# MAD.net
KiCad netlist of a schematic drawn in EAGLE
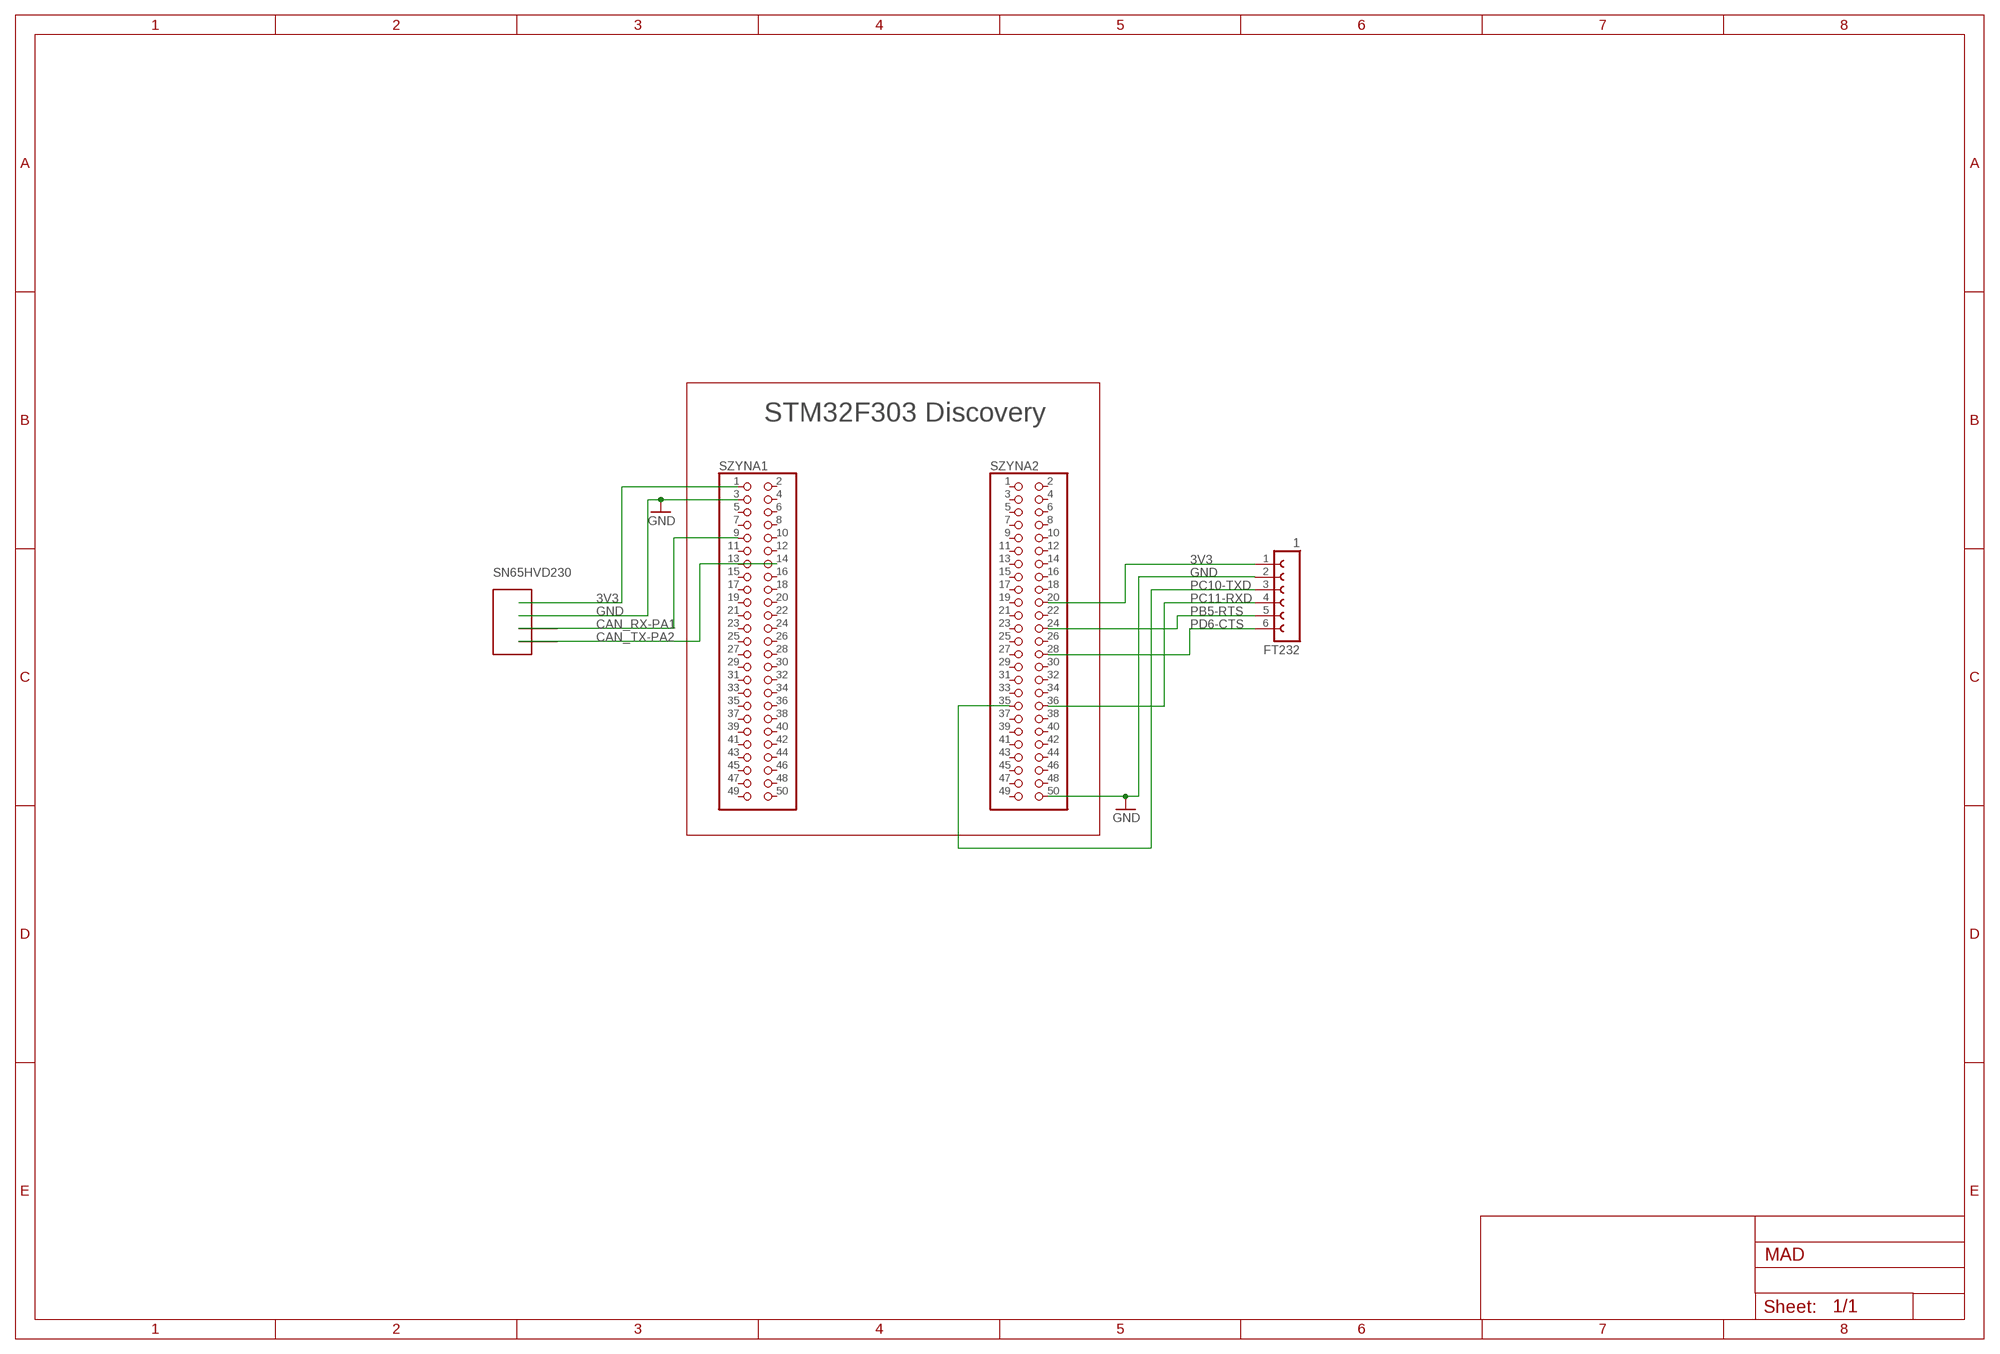
[diagram p0: schematic, sheet 1]

(export (version "E")
  (design (tool "Eeschema 10.0.6"))
  (components
    (comp (ref "FT232")
      (value "1")
      (footprint "eagle-import:FE06W")
      (libsource (lib "eagle-import") (part "FE06W"))
    )
    (comp (ref "SN65HVD230")
      (value "FE04W")
      (footprint "eagle-import:FE04")
      (libsource (lib "eagle-import") (part "FE04W"))
    )
    (comp (ref "SZYNA1")
      (value "PINHD-2X25")
      (footprint "eagle-import:2X25")
      (libsource (lib "eagle-import") (part "PINHD-2X25"))
    )
    (comp (ref "SZYNA2")
      (value "PINHD-2X25")
      (footprint "eagle-import:2X25")
      (libsource (lib "eagle-import") (part "PINHD-2X25"))
    )
  )
  (nets
    (net (code "1") (name "GND") (class "Default")
      (node (ref "FT232") (pin "2") (pinfunction "2_2") (pintype "passive"))
      (node (ref "SN65HVD230") (pin "P$2") (pinfunction "P$2_P$2") (pintype "bidirectional"))
      (node (ref "SZYNA1") (pin "3") (pinfunction "3_3") (pintype "passive"))
      (node (ref "SZYNA2") (pin "50") (pinfunction "50_50") (pintype "passive"))
    )
    (net (code "2") (name "Net-(FT232-Pad1)") (class "Default")
      (node (ref "FT232") (pin "1") (pinfunction "1_1") (pintype "passive"))
      (node (ref "SZYNA2") (pin "20") (pinfunction "20_20") (pintype "passive"))
    )
    (net (code "3") (name "Net-(FT232-Pad3)") (class "Default")
      (node (ref "FT232") (pin "3") (pinfunction "3_3") (pintype "passive"))
      (node (ref "SZYNA2") (pin "35") (pinfunction "35_35") (pintype "passive"))
    )
    (net (code "4") (name "Net-(FT232-Pad4)") (class "Default")
      (node (ref "FT232") (pin "4") (pinfunction "4_4") (pintype "passive"))
      (node (ref "SZYNA2") (pin "36") (pinfunction "36_36") (pintype "passive"))
    )
    (net (code "5") (name "Net-(FT232-Pad5)") (class "Default")
      (node (ref "FT232") (pin "5") (pinfunction "5_5") (pintype "passive"))
      (node (ref "SZYNA2") (pin "24") (pinfunction "24_24") (pintype "passive"))
    )
    (net (code "6") (name "Net-(FT232-Pad6)") (class "Default")
      (node (ref "FT232") (pin "6") (pinfunction "6_6") (pintype "passive"))
      (node (ref "SZYNA2") (pin "28") (pinfunction "28_28") (pintype "passive"))
    )
    (net (code "7") (name "Net-(SN65HVD230-PadP$1)") (class "Default")
      (node (ref "SN65HVD230") (pin "P$1") (pinfunction "P$1_P$1") (pintype "bidirectional"))
      (node (ref "SZYNA1") (pin "1") (pinfunction "1_1") (pintype "passive"))
    )
    (net (code "8") (name "Net-(SN65HVD230-PadP$3)") (class "Default")
      (node (ref "SN65HVD230") (pin "P$3") (pinfunction "P$3_P$3") (pintype "bidirectional"))
      (node (ref "SZYNA1") (pin "9") (pinfunction "9_9") (pintype "passive"))
    )
    (net (code "9") (name "Net-(SN65HVD230-PadP$4)") (class "Default")
      (node (ref "SN65HVD230") (pin "P$4") (pinfunction "P$4_P$4") (pintype "bidirectional"))
      (node (ref "SZYNA1") (pin "14") (pinfunction "14_14") (pintype "passive"))
    )
    (net (code "10") (name "unconnected-(SZYNA1-Pad2)") (class "Default")
      (node (ref "SZYNA1") (pin "2") (pinfunction "2_2") (pintype "passive"))
    )
    (net (code "11") (name "unconnected-(SZYNA1-Pad4)") (class "Default")
      (node (ref "SZYNA1") (pin "4") (pinfunction "4_4") (pintype "passive"))
    )
    (net (code "12") (name "unconnected-(SZYNA1-Pad5)") (class "Default")
      (node (ref "SZYNA1") (pin "5") (pinfunction "5_5") (pintype "passive"))
    )
    (net (code "13") (name "unconnected-(SZYNA1-Pad6)") (class "Default")
      (node (ref "SZYNA1") (pin "6") (pinfunction "6_6") (pintype "passive"))
    )
    (net (code "14") (name "unconnected-(SZYNA1-Pad7)") (class "Default")
      (node (ref "SZYNA1") (pin "7") (pinfunction "7_7") (pintype "passive"))
    )
    (net (code "15") (name "unconnected-(SZYNA1-Pad8)") (class "Default")
      (node (ref "SZYNA1") (pin "8") (pinfunction "8_8") (pintype "passive"))
    )
    (net (code "16") (name "unconnected-(SZYNA1-Pad10)") (class "Default")
      (node (ref "SZYNA1") (pin "10") (pinfunction "10_10") (pintype "passive"))
    )
    (net (code "17") (name "unconnected-(SZYNA1-Pad11)") (class "Default")
      (node (ref "SZYNA1") (pin "11") (pinfunction "11_11") (pintype "passive"))
    )
    (net (code "18") (name "unconnected-(SZYNA1-Pad12)") (class "Default")
      (node (ref "SZYNA1") (pin "12") (pinfunction "12_12") (pintype "passive"))
    )
    (net (code "19") (name "unconnected-(SZYNA1-Pad13)") (class "Default")
      (node (ref "SZYNA1") (pin "13") (pinfunction "13_13") (pintype "passive"))
    )
    (net (code "20") (name "unconnected-(SZYNA1-Pad15)") (class "Default")
      (node (ref "SZYNA1") (pin "15") (pinfunction "15_15") (pintype "passive"))
    )
    (net (code "21") (name "unconnected-(SZYNA1-Pad16)") (class "Default")
      (node (ref "SZYNA1") (pin "16") (pinfunction "16_16") (pintype "passive"))
    )
    (net (code "22") (name "unconnected-(SZYNA1-Pad17)") (class "Default")
      (node (ref "SZYNA1") (pin "17") (pinfunction "17_17") (pintype "passive"))
    )
    (net (code "23") (name "unconnected-(SZYNA1-Pad18)") (class "Default")
      (node (ref "SZYNA1") (pin "18") (pinfunction "18_18") (pintype "passive"))
    )
    (net (code "24") (name "unconnected-(SZYNA1-Pad19)") (class "Default")
      (node (ref "SZYNA1") (pin "19") (pinfunction "19_19") (pintype "passive"))
    )
    (net (code "25") (name "unconnected-(SZYNA1-Pad20)") (class "Default")
      (node (ref "SZYNA1") (pin "20") (pinfunction "20_20") (pintype "passive"))
    )
    (net (code "26") (name "unconnected-(SZYNA1-Pad21)") (class "Default")
      (node (ref "SZYNA1") (pin "21") (pinfunction "21_21") (pintype "passive"))
    )
    (net (code "27") (name "unconnected-(SZYNA1-Pad22)") (class "Default")
      (node (ref "SZYNA1") (pin "22") (pinfunction "22_22") (pintype "passive"))
    )
    (net (code "28") (name "unconnected-(SZYNA1-Pad23)") (class "Default")
      (node (ref "SZYNA1") (pin "23") (pinfunction "23_23") (pintype "passive"))
    )
    (net (code "29") (name "unconnected-(SZYNA1-Pad24)") (class "Default")
      (node (ref "SZYNA1") (pin "24") (pinfunction "24_24") (pintype "passive"))
    )
    (net (code "30") (name "unconnected-(SZYNA1-Pad25)") (class "Default")
      (node (ref "SZYNA1") (pin "25") (pinfunction "25_25") (pintype "passive"))
    )
    (net (code "31") (name "unconnected-(SZYNA1-Pad26)") (class "Default")
      (node (ref "SZYNA1") (pin "26") (pinfunction "26_26") (pintype "passive"))
    )
    (net (code "32") (name "unconnected-(SZYNA1-Pad27)") (class "Default")
      (node (ref "SZYNA1") (pin "27") (pinfunction "27_27") (pintype "passive"))
    )
    (net (code "33") (name "unconnected-(SZYNA1-Pad28)") (class "Default")
      (node (ref "SZYNA1") (pin "28") (pinfunction "28_28") (pintype "passive"))
    )
    (net (code "34") (name "unconnected-(SZYNA1-Pad29)") (class "Default")
      (node (ref "SZYNA1") (pin "29") (pinfunction "29_29") (pintype "passive"))
    )
    (net (code "35") (name "unconnected-(SZYNA1-Pad30)") (class "Default")
      (node (ref "SZYNA1") (pin "30") (pinfunction "30_30") (pintype "passive"))
    )
    (net (code "36") (name "unconnected-(SZYNA1-Pad31)") (class "Default")
      (node (ref "SZYNA1") (pin "31") (pinfunction "31_31") (pintype "passive"))
    )
    (net (code "37") (name "unconnected-(SZYNA1-Pad32)") (class "Default")
      (node (ref "SZYNA1") (pin "32") (pinfunction "32_32") (pintype "passive"))
    )
    (net (code "38") (name "unconnected-(SZYNA1-Pad33)") (class "Default")
      (node (ref "SZYNA1") (pin "33") (pinfunction "33_33") (pintype "passive"))
    )
    (net (code "39") (name "unconnected-(SZYNA1-Pad34)") (class "Default")
      (node (ref "SZYNA1") (pin "34") (pinfunction "34_34") (pintype "passive"))
    )
    (net (code "40") (name "unconnected-(SZYNA1-Pad35)") (class "Default")
      (node (ref "SZYNA1") (pin "35") (pinfunction "35_35") (pintype "passive"))
    )
    (net (code "41") (name "unconnected-(SZYNA1-Pad36)") (class "Default")
      (node (ref "SZYNA1") (pin "36") (pinfunction "36_36") (pintype "passive"))
    )
    (net (code "42") (name "unconnected-(SZYNA1-Pad37)") (class "Default")
      (node (ref "SZYNA1") (pin "37") (pinfunction "37_37") (pintype "passive"))
    )
    (net (code "43") (name "unconnected-(SZYNA1-Pad38)") (class "Default")
      (node (ref "SZYNA1") (pin "38") (pinfunction "38_38") (pintype "passive"))
    )
    (net (code "44") (name "unconnected-(SZYNA1-Pad39)") (class "Default")
      (node (ref "SZYNA1") (pin "39") (pinfunction "39_39") (pintype "passive"))
    )
    (net (code "45") (name "unconnected-(SZYNA1-Pad40)") (class "Default")
      (node (ref "SZYNA1") (pin "40") (pinfunction "40_40") (pintype "passive"))
    )
    (net (code "46") (name "unconnected-(SZYNA1-Pad41)") (class "Default")
      (node (ref "SZYNA1") (pin "41") (pinfunction "41_41") (pintype "passive"))
    )
    (net (code "47") (name "unconnected-(SZYNA1-Pad42)") (class "Default")
      (node (ref "SZYNA1") (pin "42") (pinfunction "42_42") (pintype "passive"))
    )
    (net (code "48") (name "unconnected-(SZYNA1-Pad43)") (class "Default")
      (node (ref "SZYNA1") (pin "43") (pinfunction "43_43") (pintype "passive"))
    )
    (net (code "49") (name "unconnected-(SZYNA1-Pad44)") (class "Default")
      (node (ref "SZYNA1") (pin "44") (pinfunction "44_44") (pintype "passive"))
    )
    (net (code "50") (name "unconnected-(SZYNA1-Pad45)") (class "Default")
      (node (ref "SZYNA1") (pin "45") (pinfunction "45_45") (pintype "passive"))
    )
    (net (code "51") (name "unconnected-(SZYNA1-Pad46)") (class "Default")
      (node (ref "SZYNA1") (pin "46") (pinfunction "46_46") (pintype "passive"))
    )
    (net (code "52") (name "unconnected-(SZYNA1-Pad47)") (class "Default")
      (node (ref "SZYNA1") (pin "47") (pinfunction "47_47") (pintype "passive"))
    )
    (net (code "53") (name "unconnected-(SZYNA1-Pad48)") (class "Default")
      (node (ref "SZYNA1") (pin "48") (pinfunction "48_48") (pintype "passive"))
    )
    (net (code "54") (name "unconnected-(SZYNA1-Pad49)") (class "Default")
      (node (ref "SZYNA1") (pin "49") (pinfunction "49_49") (pintype "passive"))
    )
    (net (code "55") (name "unconnected-(SZYNA1-Pad50)") (class "Default")
      (node (ref "SZYNA1") (pin "50") (pinfunction "50_50") (pintype "passive"))
    )
    (net (code "56") (name "unconnected-(SZYNA2-Pad1)") (class "Default")
      (node (ref "SZYNA2") (pin "1") (pinfunction "1_1") (pintype "passive"))
    )
    (net (code "57") (name "unconnected-(SZYNA2-Pad2)") (class "Default")
      (node (ref "SZYNA2") (pin "2") (pinfunction "2_2") (pintype "passive"))
    )
    (net (code "58") (name "unconnected-(SZYNA2-Pad3)") (class "Default")
      (node (ref "SZYNA2") (pin "3") (pinfunction "3_3") (pintype "passive"))
    )
    (net (code "59") (name "unconnected-(SZYNA2-Pad4)") (class "Default")
      (node (ref "SZYNA2") (pin "4") (pinfunction "4_4") (pintype "passive"))
    )
    (net (code "60") (name "unconnected-(SZYNA2-Pad5)") (class "Default")
      (node (ref "SZYNA2") (pin "5") (pinfunction "5_5") (pintype "passive"))
    )
    (net (code "61") (name "unconnected-(SZYNA2-Pad6)") (class "Default")
      (node (ref "SZYNA2") (pin "6") (pinfunction "6_6") (pintype "passive"))
    )
    (net (code "62") (name "unconnected-(SZYNA2-Pad7)") (class "Default")
      (node (ref "SZYNA2") (pin "7") (pinfunction "7_7") (pintype "passive"))
    )
    (net (code "63") (name "unconnected-(SZYNA2-Pad8)") (class "Default")
      (node (ref "SZYNA2") (pin "8") (pinfunction "8_8") (pintype "passive"))
    )
    (net (code "64") (name "unconnected-(SZYNA2-Pad9)") (class "Default")
      (node (ref "SZYNA2") (pin "9") (pinfunction "9_9") (pintype "passive"))
    )
    (net (code "65") (name "unconnected-(SZYNA2-Pad10)") (class "Default")
      (node (ref "SZYNA2") (pin "10") (pinfunction "10_10") (pintype "passive"))
    )
    (net (code "66") (name "unconnected-(SZYNA2-Pad11)") (class "Default")
      (node (ref "SZYNA2") (pin "11") (pinfunction "11_11") (pintype "passive"))
    )
    (net (code "67") (name "unconnected-(SZYNA2-Pad12)") (class "Default")
      (node (ref "SZYNA2") (pin "12") (pinfunction "12_12") (pintype "passive"))
    )
    (net (code "68") (name "unconnected-(SZYNA2-Pad13)") (class "Default")
      (node (ref "SZYNA2") (pin "13") (pinfunction "13_13") (pintype "passive"))
    )
    (net (code "69") (name "unconnected-(SZYNA2-Pad14)") (class "Default")
      (node (ref "SZYNA2") (pin "14") (pinfunction "14_14") (pintype "passive"))
    )
    (net (code "70") (name "unconnected-(SZYNA2-Pad15)") (class "Default")
      (node (ref "SZYNA2") (pin "15") (pinfunction "15_15") (pintype "passive"))
    )
    (net (code "71") (name "unconnected-(SZYNA2-Pad16)") (class "Default")
      (node (ref "SZYNA2") (pin "16") (pinfunction "16_16") (pintype "passive"))
    )
    (net (code "72") (name "unconnected-(SZYNA2-Pad17)") (class "Default")
      (node (ref "SZYNA2") (pin "17") (pinfunction "17_17") (pintype "passive"))
    )
    (net (code "73") (name "unconnected-(SZYNA2-Pad18)") (class "Default")
      (node (ref "SZYNA2") (pin "18") (pinfunction "18_18") (pintype "passive"))
    )
    (net (code "74") (name "unconnected-(SZYNA2-Pad19)") (class "Default")
      (node (ref "SZYNA2") (pin "19") (pinfunction "19_19") (pintype "passive"))
    )
    (net (code "75") (name "unconnected-(SZYNA2-Pad21)") (class "Default")
      (node (ref "SZYNA2") (pin "21") (pinfunction "21_21") (pintype "passive"))
    )
    (net (code "76") (name "unconnected-(SZYNA2-Pad22)") (class "Default")
      (node (ref "SZYNA2") (pin "22") (pinfunction "22_22") (pintype "passive"))
    )
    (net (code "77") (name "unconnected-(SZYNA2-Pad23)") (class "Default")
      (node (ref "SZYNA2") (pin "23") (pinfunction "23_23") (pintype "passive"))
    )
    (net (code "78") (name "unconnected-(SZYNA2-Pad25)") (class "Default")
      (node (ref "SZYNA2") (pin "25") (pinfunction "25_25") (pintype "passive"))
    )
    (net (code "79") (name "unconnected-(SZYNA2-Pad26)") (class "Default")
      (node (ref "SZYNA2") (pin "26") (pinfunction "26_26") (pintype "passive"))
    )
    (net (code "80") (name "unconnected-(SZYNA2-Pad27)") (class "Default")
      (node (ref "SZYNA2") (pin "27") (pinfunction "27_27") (pintype "passive"))
    )
    (net (code "81") (name "unconnected-(SZYNA2-Pad29)") (class "Default")
      (node (ref "SZYNA2") (pin "29") (pinfunction "29_29") (pintype "passive"))
    )
    (net (code "82") (name "unconnected-(SZYNA2-Pad30)") (class "Default")
      (node (ref "SZYNA2") (pin "30") (pinfunction "30_30") (pintype "passive"))
    )
    (net (code "83") (name "unconnected-(SZYNA2-Pad31)") (class "Default")
      (node (ref "SZYNA2") (pin "31") (pinfunction "31_31") (pintype "passive"))
    )
    (net (code "84") (name "unconnected-(SZYNA2-Pad32)") (class "Default")
      (node (ref "SZYNA2") (pin "32") (pinfunction "32_32") (pintype "passive"))
    )
    (net (code "85") (name "unconnected-(SZYNA2-Pad33)") (class "Default")
      (node (ref "SZYNA2") (pin "33") (pinfunction "33_33") (pintype "passive"))
    )
    (net (code "86") (name "unconnected-(SZYNA2-Pad34)") (class "Default")
      (node (ref "SZYNA2") (pin "34") (pinfunction "34_34") (pintype "passive"))
    )
    (net (code "87") (name "unconnected-(SZYNA2-Pad37)") (class "Default")
      (node (ref "SZYNA2") (pin "37") (pinfunction "37_37") (pintype "passive"))
    )
    (net (code "88") (name "unconnected-(SZYNA2-Pad38)") (class "Default")
      (node (ref "SZYNA2") (pin "38") (pinfunction "38_38") (pintype "passive"))
    )
    (net (code "89") (name "unconnected-(SZYNA2-Pad39)") (class "Default")
      (node (ref "SZYNA2") (pin "39") (pinfunction "39_39") (pintype "passive"))
    )
    (net (code "90") (name "unconnected-(SZYNA2-Pad40)") (class "Default")
      (node (ref "SZYNA2") (pin "40") (pinfunction "40_40") (pintype "passive"))
    )
    (net (code "91") (name "unconnected-(SZYNA2-Pad41)") (class "Default")
      (node (ref "SZYNA2") (pin "41") (pinfunction "41_41") (pintype "passive"))
    )
    (net (code "92") (name "unconnected-(SZYNA2-Pad42)") (class "Default")
      (node (ref "SZYNA2") (pin "42") (pinfunction "42_42") (pintype "passive"))
    )
    (net (code "93") (name "unconnected-(SZYNA2-Pad43)") (class "Default")
      (node (ref "SZYNA2") (pin "43") (pinfunction "43_43") (pintype "passive"))
    )
    (net (code "94") (name "unconnected-(SZYNA2-Pad44)") (class "Default")
      (node (ref "SZYNA2") (pin "44") (pinfunction "44_44") (pintype "passive"))
    )
    (net (code "95") (name "unconnected-(SZYNA2-Pad45)") (class "Default")
      (node (ref "SZYNA2") (pin "45") (pinfunction "45_45") (pintype "passive"))
    )
    (net (code "96") (name "unconnected-(SZYNA2-Pad46)") (class "Default")
      (node (ref "SZYNA2") (pin "46") (pinfunction "46_46") (pintype "passive"))
    )
    (net (code "97") (name "unconnected-(SZYNA2-Pad47)") (class "Default")
      (node (ref "SZYNA2") (pin "47") (pinfunction "47_47") (pintype "passive"))
    )
    (net (code "98") (name "unconnected-(SZYNA2-Pad48)") (class "Default")
      (node (ref "SZYNA2") (pin "48") (pinfunction "48_48") (pintype "passive"))
    )
    (net (code "99") (name "unconnected-(SZYNA2-Pad49)") (class "Default")
      (node (ref "SZYNA2") (pin "49") (pinfunction "49_49") (pintype "passive"))
    )
  )
)
